# ThermalType_Arduino_v0_1.net
KiCad netlist of a schematic drawn in Altium Designer
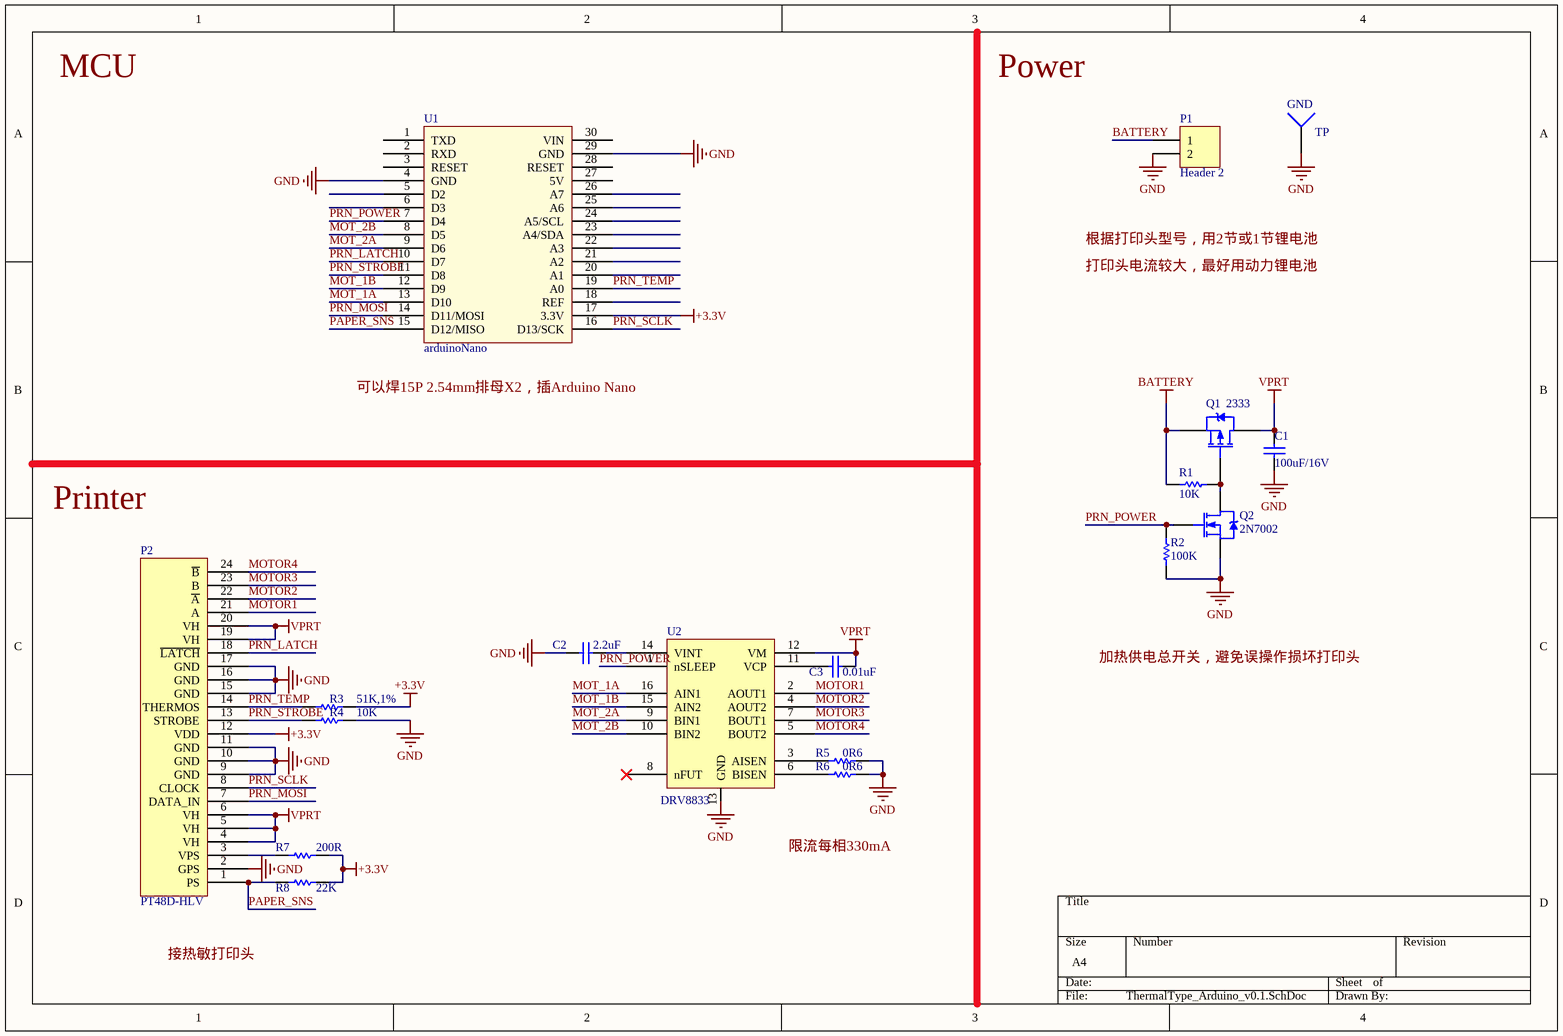
[diagram p0: ThermalType_Arduino_v0.1.SchDoc]

(export (version "E")
  (design (tool "Eeschema 10.0.6"))
  (components
    (comp (ref "C1")
      (value "100uF/16V")
      (footprint "CAP6.3*5.5")
      (description "0603C")
      (libsource (lib "mySchlib") (part "0603C"))
    )
    (comp (ref "C2")
      (value "2.2uF")
      (footprint "LC-0603_C")
      (description "0603C")
      (libsource (lib "mySchlib") (part "0603C"))
    )
    (comp (ref "C3")
      (value "0.01uF")
      (footprint "LC-0603_C")
      (description "0603C")
      (libsource (lib "mySchlib") (part "0603C"))
    )
    (comp (ref "GND")
      (value "TP")
      (footprint "TP")
      (description "Socket")
      (fields (field (name "PUBLISHER") "Altium Limited"))
      (libsource (lib "Miscellaneous Connectors") (part "Socket"))
    )
    (comp (ref "P1")
      (value "Header 2")
      (footprint "YX-XH-2-2.54-90")
      (description "Header, 2-Pin")
      (fields (field (name "PUBLISHER") "Altium Limited"))
      (libsource (lib "Miscellaneous Connectors") (part "Header 2"))
    )
    (comp (ref "P2") (value "PT48D-HLV") (libsource (lib "mySchlib") (part "PT48D-HLV")))
    (comp (ref "Q1")
      (value "2333")
      (footprint "LC-SOT-23(SOT-23-3)")
      (description "P-MOS")
      (libsource (lib "mySchlib") (part "SI2333"))
    )
    (comp (ref "Q2")
      (value "2N7002")
      (footprint "LC-SOT-23(SOT-23-3)")
      (description "N-Channel Power MOSFET")
      (fields (field (name "PUBLISHER") "Altium Limited"))
      (libsource (lib "PCB_Project1") (part "NMOS-2"))
    )
    (comp (ref "R1")
      (value "10K")
      (footprint "LC-0603_R")
      (description "0603R")
      (libsource (lib "mySchlib") (part "0603R"))
    )
    (comp (ref "R2")
      (value "100K")
      (footprint "LC-0603_R")
      (description "0603R")
      (libsource (lib "mySchlib") (part "0603R"))
    )
    (comp (ref "R3")
      (value "51K,1%")
      (footprint "LC-0603_R")
      (description "0603R")
      (libsource (lib "mySchlib") (part "0603R"))
    )
    (comp (ref "R4")
      (value "10K")
      (footprint "LC-0603_R")
      (description "0603R")
      (libsource (lib "mySchlib") (part "0603R"))
    )
    (comp (ref "R5")
      (value "0R6")
      (footprint "LC-0805_R")
      (description "0603R")
      (libsource (lib "mySchlib") (part "0603R"))
    )
    (comp (ref "R6")
      (value "0R6")
      (footprint "LC-0805_R")
      (description "0603R")
      (libsource (lib "mySchlib") (part "0603R"))
    )
    (comp (ref "R7")
      (value "200R")
      (footprint "LC-0603_R")
      (description "0603R")
      (libsource (lib "mySchlib") (part "0603R"))
    )
    (comp (ref "R8")
      (value "22K")
      (footprint "LC-0603_R")
      (description "0603R")
      (libsource (lib "mySchlib") (part "0603R"))
    )
    (comp (ref "U1")
      (value "arduinoNano")
      (footprint "Arduino nano")
      (libsource (lib "mySchlib") (part "arduinoNano"))
    )
    (comp (ref "U2") (value "DRV8833") (footprint "HTSSOP-16") (libsource (lib "mySchlib") (part "DRV8833")))
  )
  (nets
    (net (code "1") (name "+3.3V") (class "Default")
      (node (ref "P2") (pin "12") (pinfunction "VDD_12") (pintype "passive"))
      (node (ref "R3") (pin "2") (pinfunction "2_2") (pintype "passive"))
      (node (ref "R7") (pin "2") (pinfunction "2_2") (pintype "passive"))
      (node (ref "R8") (pin "2") (pinfunction "2_2") (pintype "passive"))
      (node (ref "U1") (pin "17") (pinfunction "3.3V_17") (pintype "passive"))
    )
    (net (code "2") (name "/MOTOR1") (class "Default")
      (node (ref "P2") (pin "21") (pinfunction "A_21") (pintype "passive"))
      (node (ref "U2") (pin "2") (pinfunction "AOUT1_2") (pintype "passive"))
    )
    (net (code "3") (name "/MOTOR2") (class "Default")
      (node (ref "P2") (pin "22") (pinfunction "~{A}_22") (pintype "passive"))
      (node (ref "U2") (pin "4") (pinfunction "AOUT2_4") (pintype "passive"))
    )
    (net (code "4") (name "/MOTOR3") (class "Default")
      (node (ref "P2") (pin "23") (pinfunction "B_23") (pintype "passive"))
      (node (ref "U2") (pin "7") (pinfunction "BOUT1_7") (pintype "passive"))
    )
    (net (code "5") (name "/MOTOR4") (class "Default")
      (node (ref "P2") (pin "24") (pinfunction "~{B}_24") (pintype "passive"))
      (node (ref "U2") (pin "5") (pinfunction "BOUT2_5") (pintype "passive"))
    )
    (net (code "6") (name "/MOT_1A") (class "Default")
      (node (ref "U1") (pin "13") (pinfunction "D10_13") (pintype "passive"))
      (node (ref "U2") (pin "16") (pinfunction "AIN1_16") (pintype "passive"))
    )
    (net (code "7") (name "/MOT_1B") (class "Default")
      (node (ref "U1") (pin "12") (pinfunction "D9_12") (pintype "passive"))
      (node (ref "U2") (pin "15") (pinfunction "AIN2_15") (pintype "passive"))
    )
    (net (code "8") (name "/MOT_2A") (class "Default")
      (node (ref "U1") (pin "9") (pinfunction "D6_9") (pintype "passive"))
      (node (ref "U2") (pin "9") (pinfunction "BIN1_9") (pintype "passive"))
    )
    (net (code "9") (name "/MOT_2B") (class "Default")
      (node (ref "U1") (pin "8") (pinfunction "D5_8") (pintype "passive"))
      (node (ref "U2") (pin "10") (pinfunction "BIN2_10") (pintype "passive"))
    )
    (net (code "10") (name "/PAPER_SNS") (class "Default")
      (node (ref "P2") (pin "1") (pinfunction "PS_1") (pintype "passive"))
      (node (ref "R8") (pin "1") (pinfunction "1_1") (pintype "passive"))
      (node (ref "U1") (pin "15") (pinfunction "D12/MISO_15") (pintype "passive"))
    )
    (net (code "11") (name "/PRN_LATCH") (class "Default")
      (node (ref "P2") (pin "18") (pinfunction "~{LATCH}_18") (pintype "passive"))
      (node (ref "U1") (pin "10") (pinfunction "D7_10") (pintype "passive"))
    )
    (net (code "12") (name "/PRN_MOSI") (class "Default")
      (node (ref "P2") (pin "7") (pinfunction "DATA_IN_7") (pintype "passive"))
      (node (ref "U1") (pin "14") (pinfunction "D11/MOSI_14") (pintype "passive"))
    )
    (net (code "13") (name "/PRN_POWER") (class "Default")
      (node (ref "Q2") (pin "1") (pinfunction "G_1") (pintype "passive"))
      (node (ref "R2") (pin "1") (pinfunction "1_1") (pintype "passive"))
      (node (ref "U1") (pin "7") (pinfunction "D4_7") (pintype "passive"))
      (node (ref "U2") (pin "1") (pinfunction "nSLEEP_1") (pintype "passive"))
    )
    (net (code "14") (name "/PRN_SCLK") (class "Default")
      (node (ref "P2") (pin "8") (pinfunction "CLOCK_8") (pintype "passive"))
      (node (ref "U1") (pin "16") (pinfunction "D13/SCK_16") (pintype "passive"))
    )
    (net (code "15") (name "/PRN_STROBE") (class "Default")
      (node (ref "P2") (pin "13") (pinfunction "STROBE_13") (pintype "passive"))
      (node (ref "R4") (pin "1") (pinfunction "1_1") (pintype "passive"))
      (node (ref "U1") (pin "11") (pinfunction "D8_11") (pintype "passive"))
    )
    (net (code "16") (name "/PRN_TEMP") (class "Default")
      (node (ref "P2") (pin "14") (pinfunction "THERMOS_14") (pintype "passive"))
      (node (ref "R3") (pin "1") (pinfunction "1_1") (pintype "passive"))
      (node (ref "U1") (pin "19") (pinfunction "A0_19") (pintype "passive"))
    )
    (net (code "17") (name "BATTERY") (class "Default")
      (node (ref "P1") (pin "1") (pinfunction "1_1") (pintype "passive"))
      (node (ref "Q1") (pin "3") (pinfunction "S_3") (pintype "passive"))
      (node (ref "R1") (pin "2") (pinfunction "2_2") (pintype "passive"))
    )
    (net (code "18") (name "GND") (class "Default")
      (node (ref "C1") (pin "2") (pinfunction "2_2") (pintype "passive"))
      (node (ref "C2") (pin "2") (pinfunction "2_2") (pintype "passive"))
      (node (ref "GND") (pin "1") (pinfunction "1_1") (pintype "passive"))
      (node (ref "P1") (pin "2") (pinfunction "2_2") (pintype "passive"))
      (node (ref "P2") (pin "10") (pinfunction "GND_10") (pintype "passive"))
      (node (ref "P2") (pin "11") (pinfunction "GND_11") (pintype "passive"))
      (node (ref "P2") (pin "15") (pinfunction "GND_15") (pintype "passive"))
      (node (ref "P2") (pin "16") (pinfunction "GND_16") (pintype "passive"))
      (node (ref "P2") (pin "17") (pinfunction "GND_17") (pintype "passive"))
      (node (ref "P2") (pin "2") (pinfunction "GPS_2") (pintype "passive"))
      (node (ref "P2") (pin "9") (pinfunction "GND_9") (pintype "passive"))
      (node (ref "Q2") (pin "2") (pinfunction "S_2") (pintype "passive"))
      (node (ref "R2") (pin "2") (pinfunction "2_2") (pintype "passive"))
      (node (ref "R4") (pin "2") (pinfunction "2_2") (pintype "passive"))
      (node (ref "R5") (pin "1") (pinfunction "1_1") (pintype "passive"))
      (node (ref "R6") (pin "1") (pinfunction "1_1") (pintype "passive"))
      (node (ref "U1") (pin "29") (pinfunction "GND_29") (pintype "passive"))
      (node (ref "U1") (pin "4") (pinfunction "GND_4") (pintype "passive"))
      (node (ref "U2") (pin "13") (pinfunction "GND_13") (pintype "passive"))
    )
    (net (code "19") (name "Net-(P2-VPS)") (class "Default")
      (node (ref "P2") (pin "3") (pinfunction "VPS_3") (pintype "passive"))
      (node (ref "R7") (pin "1") (pinfunction "1_1") (pintype "passive"))
    )
    (net (code "20") (name "Net-(Q1-G)") (class "Default")
      (node (ref "Q1") (pin "1") (pinfunction "G_1") (pintype "passive"))
      (node (ref "Q2") (pin "3") (pinfunction "D_3") (pintype "passive"))
      (node (ref "R1") (pin "1") (pinfunction "1_1") (pintype "passive"))
    )
    (net (code "21") (name "Net-(U2-AISEN)") (class "Default")
      (node (ref "R5") (pin "2") (pinfunction "2_2") (pintype "passive"))
      (node (ref "U2") (pin "3") (pinfunction "AISEN_3") (pintype "passive"))
    )
    (net (code "22") (name "Net-(U2-BISEN)") (class "Default")
      (node (ref "R6") (pin "2") (pinfunction "2_2") (pintype "passive"))
      (node (ref "U2") (pin "6") (pinfunction "BISEN_6") (pintype "passive"))
    )
    (net (code "23") (name "Net-(U2-VCP)") (class "Default")
      (node (ref "C3") (pin "2") (pinfunction "2_2") (pintype "passive"))
      (node (ref "U2") (pin "11") (pinfunction "VCP_11") (pintype "passive"))
    )
    (net (code "24") (name "Net-(U2-VINT)") (class "Default")
      (node (ref "C2") (pin "1") (pinfunction "1_1") (pintype "passive"))
      (node (ref "U2") (pin "14") (pinfunction "VINT_14") (pintype "passive"))
    )
    (net (code "25") (name "VPRT") (class "Default")
      (node (ref "C1") (pin "1") (pinfunction "1_1") (pintype "passive"))
      (node (ref "C3") (pin "1") (pinfunction "1_1") (pintype "passive"))
      (node (ref "P2") (pin "19") (pinfunction "VH_19") (pintype "passive"))
      (node (ref "P2") (pin "20") (pinfunction "VH_20") (pintype "passive"))
      (node (ref "P2") (pin "4") (pinfunction "VH_4") (pintype "passive"))
      (node (ref "P2") (pin "5") (pinfunction "VH_5") (pintype "passive"))
      (node (ref "P2") (pin "6") (pinfunction "VH_6") (pintype "passive"))
      (node (ref "Q1") (pin "2") (pinfunction "D_2") (pintype "passive"))
      (node (ref "U2") (pin "12") (pinfunction "VM_12") (pintype "passive"))
    )
    (net (code "26") (name "unconnected-(U1-5V-Pad27)") (class "Default")
      (node (ref "U1") (pin "27") (pinfunction "5V_27") (pintype "passive"))
    )
    (net (code "27") (name "unconnected-(U1-A1-Pad20)") (class "Default")
      (node (ref "U1") (pin "20") (pinfunction "A1_20") (pintype "passive"))
    )
    (net (code "28") (name "unconnected-(U1-A2-Pad21)") (class "Default")
      (node (ref "U1") (pin "21") (pinfunction "A2_21") (pintype "passive"))
    )
    (net (code "29") (name "unconnected-(U1-A3-Pad22)") (class "Default")
      (node (ref "U1") (pin "22") (pinfunction "A3_22") (pintype "passive"))
    )
    (net (code "30") (name "unconnected-(U1-A4{slash}SDA-Pad23)") (class "Default")
      (node (ref "U1") (pin "23") (pinfunction "A4/SDA_23") (pintype "passive"))
    )
    (net (code "31") (name "unconnected-(U1-A5{slash}SCL-Pad24)") (class "Default")
      (node (ref "U1") (pin "24") (pinfunction "A5/SCL_24") (pintype "passive"))
    )
    (net (code "32") (name "unconnected-(U1-A6-Pad25)") (class "Default")
      (node (ref "U1") (pin "25") (pinfunction "A6_25") (pintype "passive"))
    )
    (net (code "33") (name "unconnected-(U1-A7-Pad26)") (class "Default")
      (node (ref "U1") (pin "26") (pinfunction "A7_26") (pintype "passive"))
    )
    (net (code "34") (name "unconnected-(U1-D2-Pad5)") (class "Default")
      (node (ref "U1") (pin "5") (pinfunction "D2_5") (pintype "passive"))
    )
    (net (code "35") (name "unconnected-(U1-D3-Pad6)") (class "Default")
      (node (ref "U1") (pin "6") (pinfunction "D3_6") (pintype "passive"))
    )
    (net (code "36") (name "unconnected-(U1-REF-Pad18)") (class "Default")
      (node (ref "U1") (pin "18") (pinfunction "REF_18") (pintype "passive"))
    )
    (net (code "37") (name "unconnected-(U1-RESET-Pad3)") (class "Default")
      (node (ref "U1") (pin "3") (pinfunction "RESET_3") (pintype "passive"))
    )
    (net (code "38") (name "unconnected-(U1-RESET-Pad28)") (class "Default")
      (node (ref "U1") (pin "28") (pinfunction "RESET_28") (pintype "passive"))
    )
    (net (code "39") (name "unconnected-(U1-RXD-Pad2)") (class "Default")
      (node (ref "U1") (pin "2") (pinfunction "RXD_2") (pintype "passive"))
    )
    (net (code "40") (name "unconnected-(U1-TXD-Pad1)") (class "Default")
      (node (ref "U1") (pin "1") (pinfunction "TXD_1") (pintype "passive"))
    )
    (net (code "41") (name "unconnected-(U1-VIN-Pad30)") (class "Default")
      (node (ref "U1") (pin "30") (pinfunction "VIN_30") (pintype "passive"))
    )
    (net (code "42") (name "unconnected-(U2-nFUT-Pad8)") (class "Default")
      (node (ref "U2") (pin "8") (pinfunction "nFUT_8") (pintype "passive+no_connect"))
    )
  )
)
